# Microphone.net
KiCad netlist of a schematic drawn in Altium Designer
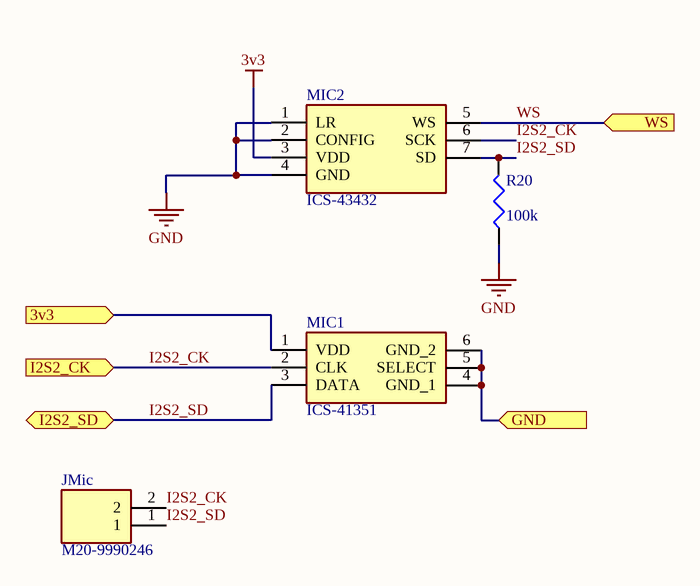
[diagram p0: Microphone.SchDoc]

(export (version "E")
  (design (tool "Eeschema 10.0.6"))
  (components
    (comp (ref "JMic")
      (value "M20-9990246")
      (footprint "SamacSys:HDRV2W66P0X254_1X2_508X254X874P")
      (description "Connector")
      (fields (field (name "MOUSER PART NUMBER") "855-M20-9990246"))
      (libsource (lib "*") (part "M20-9990246"))
    )
    (comp (ref "MIC1")
      (value "ICS-41351")
      (footprint "SamacSys:ICS41351")
      (description "Microphone")
      (fields (field (name "MOUSER PART NUMBER") "410-ICS-41351"))
      (libsource (lib "*") (part "ICS-41351"))
    )
    (comp (ref "MIC2")
      (value "ICS-43432")
      (footprint "SamacSys:ICS43432")
      (description "Integrated Circuit")
      (fields (field (name "MOUSER PART NUMBER") "410-ICS-43432"))
      (libsource (lib "*") (part "ICS-43432"))
    )
    (comp (ref "R20")
      (value "100k")
      (footprint "J1-0603")
      (description "Resistor")
      (fields (field (name "Comment") "Res3") (field (name "PUBLISHER") "Altium Limited"))
      (libsource (lib "Miscellaneous Devices") (part "Res3"))
    )
  )
  (nets
    (net (code "1") (name "/I2S2_CK") (class "Default")
      (node (ref "JMic") (pin "2") (pinfunction "2_2") (pintype "passive"))
      (node (ref "MIC1") (pin "2") (pinfunction "CLK_2") (pintype "passive"))
      (node (ref "MIC2") (pin "6") (pinfunction "SCK_6") (pintype "passive"))
    )
    (net (code "2") (name "/I2S2_SD") (class "Default")
      (node (ref "JMic") (pin "1") (pinfunction "1_1") (pintype "passive"))
      (node (ref "MIC1") (pin "3") (pinfunction "DATA_3") (pintype "passive"))
      (node (ref "MIC2") (pin "7") (pinfunction "SD_7") (pintype "passive"))
      (node (ref "R20") (pin "2") (pinfunction "2_2") (pintype "passive"))
    )
    (net (code "3") (name "/WS") (class "Default")
      (node (ref "MIC2") (pin "5") (pinfunction "WS_5") (pintype "passive"))
    )
    (net (code "4") (name "3v3") (class "Default")
      (node (ref "MIC1") (pin "1") (pinfunction "VDD_1") (pintype "passive"))
      (node (ref "MIC2") (pin "3") (pinfunction "VDD_3") (pintype "passive"))
    )
    (net (code "5") (name "GND") (class "Default")
      (node (ref "MIC1") (pin "4") (pinfunction "GND_1_4") (pintype "passive"))
      (node (ref "MIC1") (pin "5") (pinfunction "SELECT_5") (pintype "passive"))
      (node (ref "MIC1") (pin "6") (pinfunction "GND_2_6") (pintype "passive"))
      (node (ref "MIC2") (pin "1") (pinfunction "LR_1") (pintype "passive"))
      (node (ref "MIC2") (pin "2") (pinfunction "CONFIG_2") (pintype "passive"))
      (node (ref "MIC2") (pin "4") (pinfunction "GND_4") (pintype "passive"))
      (node (ref "R20") (pin "1") (pinfunction "1_1") (pintype "passive"))
    )
  )
)
